# Board.net
KiCad netlist of a schematic drawn in EAGLE
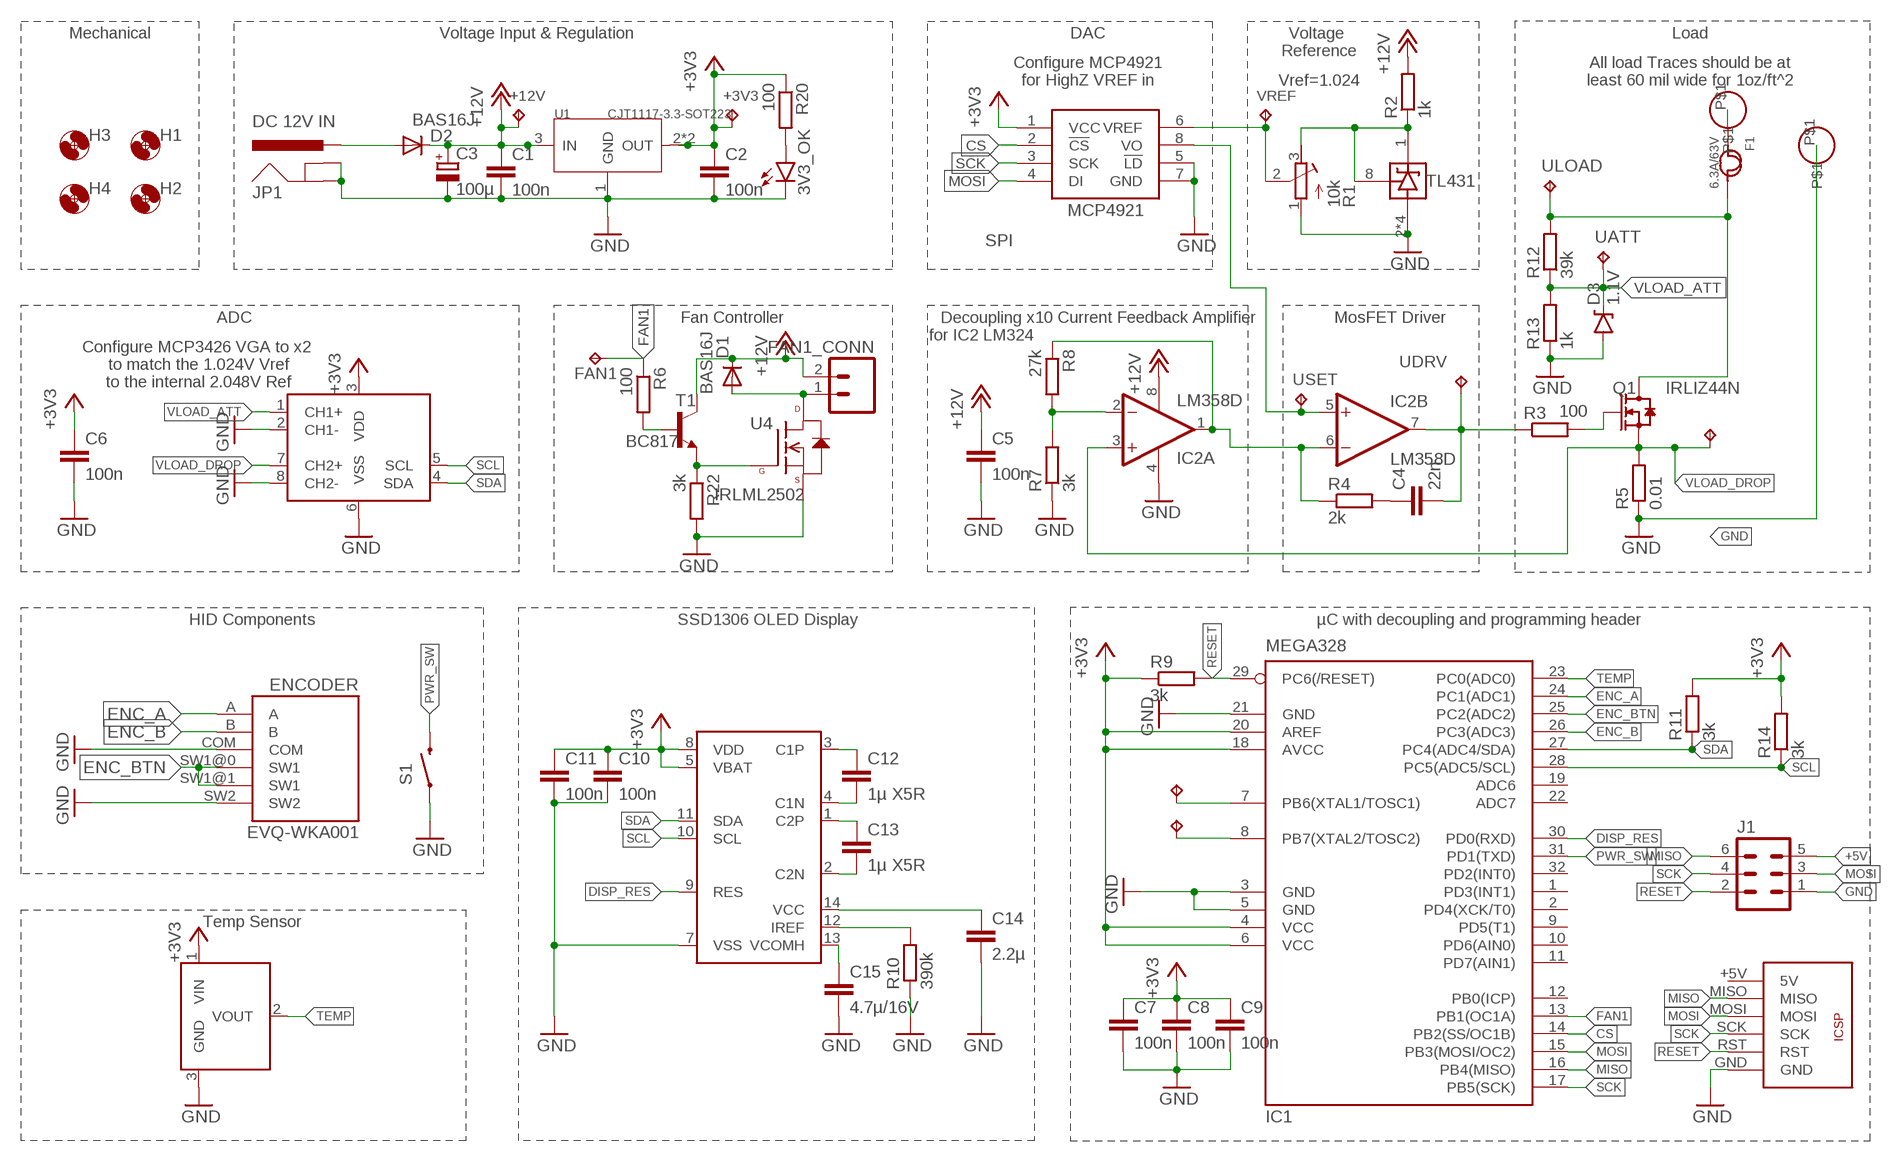
[diagram p0: schematic, sheet 1]

(export (version "E")
  (design (tool "Eeschema 10.0.6"))
  (components
    (comp (ref "+3V3")
      (value "TPB1,27")
      (footprint "eagle-import:B1,27")
      (libsource (lib "eagle-import") (part "TPB1,27"))
    )
    (comp (ref "+12V")
      (value "TPB1,27")
      (footprint "eagle-import:B1,27")
      (libsource (lib "eagle-import") (part "TPB1,27"))
    )
    (comp (ref "3V3_OK")
      (value "LED0603")
      (footprint "eagle-import:LED-0603")
      (libsource (lib "eagle-import") (part "LED0603"))
    )
    (comp (ref "C1")
      (value "100n")
      (footprint "eagle-import:C0603")
      (libsource (lib "eagle-import") (part "C-EUC0603"))
    )
    (comp (ref "C2")
      (value "100n")
      (footprint "eagle-import:C0603")
      (libsource (lib "eagle-import") (part "C-EUC0603"))
    )
    (comp (ref "C3")
      (value "100µ")
      (footprint "eagle-import:153CLV-0405")
      (libsource (lib "eagle-import") (part "CPOL-EU153CLV-0405"))
    )
    (comp (ref "C4")
      (value "22n")
      (footprint "eagle-import:C0603")
      (libsource (lib "eagle-import") (part "C-EUC0603"))
    )
    (comp (ref "C5")
      (value "100n")
      (footprint "eagle-import:C0603")
      (libsource (lib "eagle-import") (part "C-EUC0603"))
    )
    (comp (ref "C6")
      (value "100n")
      (footprint "eagle-import:C0603")
      (libsource (lib "eagle-import") (part "rcl_334_C-EUC0603"))
    )
    (comp (ref "C7")
      (value "100n")
      (footprint "eagle-import:C0603")
      (libsource (lib "eagle-import") (part "C-EUC0603"))
    )
    (comp (ref "C8")
      (value "100n")
      (footprint "eagle-import:C0603")
      (libsource (lib "eagle-import") (part "C-EUC0603"))
    )
    (comp (ref "C9")
      (value "100n")
      (footprint "eagle-import:C0603")
      (libsource (lib "eagle-import") (part "C-EUC0603"))
    )
    (comp (ref "C10")
      (value "100n")
      (footprint "eagle-import:C0603")
      (libsource (lib "eagle-import") (part "C-EUC0603"))
    )
    (comp (ref "C11")
      (value "100n")
      (footprint "eagle-import:C0603")
      (libsource (lib "eagle-import") (part "C-EUC0603"))
    )
    (comp (ref "C12")
      (value "1µ X5R")
      (footprint "eagle-import:C0603")
      (libsource (lib "eagle-import") (part "C-EUC0603"))
    )
    (comp (ref "C13")
      (value "1µ X5R")
      (footprint "eagle-import:C0603")
      (libsource (lib "eagle-import") (part "C-EUC0603"))
    )
    (comp (ref "C14")
      (value "2.2µ")
      (footprint "eagle-import:C0603")
      (libsource (lib "eagle-import") (part "C-EUC0603"))
    )
    (comp (ref "C15")
      (value "4.7µ/16V")
      (footprint "eagle-import:C0603")
      (libsource (lib "eagle-import") (part "C-EUC0603"))
    )
    (comp (ref "D1")
      (value "BAS16J")
      (footprint "eagle-import:SOD323-W")
      (libsource (lib "eagle-import") (part "DIODE-SOD323-W"))
    )
    (comp (ref "D2")
      (value "BAS16J")
      (footprint "eagle-import:SOD323-W")
      (libsource (lib "eagle-import") (part "DIODE-SOD323-W"))
    )
    (comp (ref "D3")
      (value "1.1V")
      (footprint "eagle-import:SOD-323")
      (libsource (lib "eagle-import") (part "DIODE-ZENER5.6V"))
    )
    (comp (ref "ENCODER")
      (value "EVQ-WKA001")
      (footprint "eagle-import:EVQ-WKA001")
      (libsource (lib "eagle-import") (part "EVQ-WKA001"))
    )
    (comp (ref "F1")
      (value "6.3A/63V")
      (footprint "eagle-import:F1206")
      (libsource (lib "eagle-import") (part "FUSE'1206'"))
    )
    (comp (ref "FAN1")
      (value "TPB1,27")
      (footprint "eagle-import:B1,27")
      (libsource (lib "eagle-import") (part "TPB1,27"))
    )
    (comp (ref "FAN1_CONN")
      (value "M02POLAR")
      (footprint "eagle-import:MOLEX-1X2")
      (libsource (lib "eagle-import") (part "M02POLAR"))
    )
    (comp (ref "H1")
      (value "MOUNT-HOLE3.0")
      (footprint "eagle-import:3,0")
      (libsource (lib "eagle-import") (part "MOUNT-HOLE3.0"))
    )
    (comp (ref "H2")
      (value "MOUNT-HOLE3.0")
      (footprint "eagle-import:3,0")
      (libsource (lib "eagle-import") (part "MOUNT-HOLE3.0"))
    )
    (comp (ref "H3")
      (value "MOUNT-HOLE3.0")
      (footprint "eagle-import:3,0")
      (libsource (lib "eagle-import") (part "MOUNT-HOLE3.0"))
    )
    (comp (ref "H4")
      (value "MOUNT-HOLE3.0")
      (footprint "eagle-import:3,0")
      (libsource (lib "eagle-import") (part "MOUNT-HOLE3.0"))
    )
    (comp (ref "IC1")
      (value "MEGA328")
      (footprint "eagle-import:TQFP32-08")
      (fields (field (name "MPN") "ATMEGA8-16AU"))
      (libsource (lib "eagle-import") (part "MEGA8-AI"))
    )
    (comp (ref "IC2")
      (value "LM358D")
      (footprint "eagle-import:SO08")
      (libsource (lib "eagle-import") (part "LM358D"))
    )
    (comp (ref "IC4")
      (value "MCP3426")
      (footprint "eagle-import:SO08")
      (libsource (lib "eagle-import") (part "MCP3426"))
    )
    (comp (ref "IC6")
      (value "MCP4921")
      (footprint "eagle-import:SO-8")
      (libsource (lib "eagle-import") (part "MCP4921"))
    )
    (comp (ref "IC7")
      (value "TL431CD")
      (footprint "eagle-import:SO-8")
      (libsource (lib "eagle-import") (part "TL431CD"))
    )
    (comp (ref "IN+")
      (value "6MM-BANANA-MOUNTINGHOLE")
      (footprint "eagle-import:6MM-BANANA-MOUNT")
      (libsource (lib "eagle-import") (part "6MM-BANANA-MOUNTINGHOLE"))
    )
    (comp (ref "IN-")
      (value "6MM-BANANA-MOUNTINGHOLE")
      (footprint "eagle-import:6MM-BANANA-MOUNT")
      (libsource (lib "eagle-import") (part "6MM-BANANA-MOUNTINGHOLE"))
    )
    (comp (ref "J1")
      (value "MA03-2")
      (footprint "eagle-import:MA03-2")
      (libsource (lib "eagle-import") (part "MA03-2"))
    )
    (comp (ref "JP1")
      (value "DC 12V IN")
      (footprint "eagle-import:POWER_JACK_PTH")
      (libsource (lib "eagle-import") (part "POWER_JACKPTH"))
    )
    (comp (ref "Q1")
      (value "IRLIZ44N")
      (footprint "eagle-import:TO-220H")
      (libsource (lib "eagle-import") (part "IRF3710"))
    )
    (comp (ref "R1")
      (value "10k")
      (footprint "eagle-import:RTRIM3296W")
      (libsource (lib "eagle-import") (part "R-TRIMM3296W"))
    )
    (comp (ref "R2")
      (value "1k")
      (footprint "eagle-import:R0603")
      (libsource (lib "eagle-import") (part "R-EU_R0603"))
    )
    (comp (ref "R3")
      (value "100")
      (footprint "eagle-import:R0603")
      (libsource (lib "eagle-import") (part "R-EU_R0603"))
    )
    (comp (ref "R4")
      (value "2k")
      (footprint "eagle-import:R0603")
      (libsource (lib "eagle-import") (part "R-EU_R0603"))
    )
    (comp (ref "R5")
      (value "0.01")
      (footprint "eagle-import:R2512")
      (libsource (lib "eagle-import") (part "R-EU_R2512"))
    )
    (comp (ref "R6")
      (value "100")
      (footprint "eagle-import:R0603")
      (libsource (lib "eagle-import") (part "rcl_334_R-EU_R0603"))
    )
    (comp (ref "R7")
      (value "3k")
      (footprint "eagle-import:R0603")
      (libsource (lib "eagle-import") (part "R-EU_R0603"))
    )
    (comp (ref "R8")
      (value "27k")
      (footprint "eagle-import:R0603")
      (libsource (lib "eagle-import") (part "R-EU_R0603"))
    )
    (comp (ref "R9")
      (value "3k")
      (footprint "eagle-import:R0603")
      (libsource (lib "eagle-import") (part "rcl_334_R-EU_R0603"))
    )
    (comp (ref "R10")
      (value "390k")
      (footprint "eagle-import:R0603")
      (libsource (lib "eagle-import") (part "R-EU_R0603"))
    )
    (comp (ref "R11")
      (value "3k")
      (footprint "eagle-import:R0603")
      (libsource (lib "eagle-import") (part "rcl_334_R-EU_R0603"))
    )
    (comp (ref "R12")
      (value "39k")
      (footprint "eagle-import:R0603")
      (libsource (lib "eagle-import") (part "R-EU_R0603"))
    )
    (comp (ref "R13")
      (value "1k")
      (footprint "eagle-import:R0603")
      (libsource (lib "eagle-import") (part "R-EU_R0603"))
    )
    (comp (ref "R14")
      (value "3k")
      (footprint "eagle-import:R0603")
      (libsource (lib "eagle-import") (part "rcl_334_R-EU_R0603"))
    )
    (comp (ref "R20")
      (value "100")
      (footprint "eagle-import:R0603")
      (libsource (lib "eagle-import") (part "R-EU_R0603"))
    )
    (comp (ref "R22")
      (value "3k")
      (footprint "eagle-import:R0603")
      (libsource (lib "eagle-import") (part "R-EU_R0603"))
    )
    (comp (ref "S1")
      (value "SWITCH-MOMENTARY-2SMD-1101NE")
      (footprint "eagle-import:TACTILE-SWITCH-1101NE")
      (libsource (lib "eagle-import") (part "SWITCH-MOMENTARY-2SMD-1101NE"))
    )
    (comp (ref "T1")
      (value "BC817")
      (footprint "eagle-import:SOT23-BEC")
      (libsource (lib "eagle-import") (part "-NPN-SOT23-BECBC817"))
    )
    (comp (ref "U$2")
      (value "0.86\"-OLEDBENT")
      (footprint "eagle-import:0.86_-OLED-BENT")
      (libsource (lib "eagle-import") (part "0.86{dblquote}-OLEDBENT"))
    )
    (comp (ref "U$4")
      (value "ICSP")
      (footprint "eagle-import:ICSP-SMD-NOSILK")
      (libsource (lib "eagle-import") (part "ICSP"))
    )
    (comp (ref "U1")
      (value "CJT1117-3.3-SOT223")
      (footprint "eagle-import:SOT-223")
      (fields (field (name "MPN") "CJT1117-3.3"))
      (libsource (lib "eagle-import") (part "PMIC-CJT1117-3.3(SOT223)"))
    )
    (comp (ref "U3")
      (value "MCP9701AT-E/TT")
      (footprint "eagle-import:SOT32-3")
      (libsource (lib "eagle-import") (part "MCP9701AT-E/TT"))
    )
    (comp (ref "U4")
      (value "IRLML2502")
      (footprint "eagle-import:SOT23-3")
      (libsource (lib "eagle-import") (part "N-CHANNEL-MOSFET-BSS138"))
    )
    (comp (ref "UATT")
      (value "TPB1,27")
      (footprint "eagle-import:B1,27")
      (libsource (lib "eagle-import") (part "TPB1,27"))
    )
    (comp (ref "UDROP")
      (value "TPB1,27")
      (footprint "eagle-import:B1,27")
      (libsource (lib "eagle-import") (part "TPB1,27"))
    )
    (comp (ref "UDRV")
      (value "TPB1,27")
      (footprint "eagle-import:B1,27")
      (libsource (lib "eagle-import") (part "TPB1,27"))
    )
    (comp (ref "ULOAD")
      (value "TPB1,27")
      (footprint "eagle-import:B1,27")
      (libsource (lib "eagle-import") (part "TPB1,27"))
    )
    (comp (ref "USET")
      (value "TPB1,27")
      (footprint "eagle-import:B1,27")
      (libsource (lib "eagle-import") (part "TPB1,27"))
    )
    (comp (ref "VREF")
      (value "TPB1,27")
      (footprint "eagle-import:B1,27")
      (libsource (lib "eagle-import") (part "TPB1,27"))
    )
    (comp (ref "XTAL1")
      (value "TPB1,27")
      (footprint "eagle-import:B1,27")
      (libsource (lib "eagle-import") (part "TPB1,27"))
    )
    (comp (ref "XTAL2")
      (value "TPB1,27")
      (footprint "eagle-import:B1,27")
      (libsource (lib "eagle-import") (part "TPB1,27"))
    )
  )
  (nets
    (net (code "1") (name "+3V3") (class "Default")
      (node (ref "+3V3") (pin "TP") (pinfunction "TP_TP") (pintype "input"))
      (node (ref "C10") (pin "1") (pinfunction "1_1") (pintype "passive"))
      (node (ref "C11") (pin "1") (pinfunction "1_1") (pintype "passive"))
      (node (ref "C2") (pin "1") (pinfunction "1_1") (pintype "passive"))
      (node (ref "C6") (pin "1") (pinfunction "1_1") (pintype "passive"))
      (node (ref "C7") (pin "1") (pinfunction "1_1") (pintype "passive"))
      (node (ref "C8") (pin "1") (pinfunction "1_1") (pintype "passive"))
      (node (ref "C9") (pin "1") (pinfunction "1_1") (pintype "passive"))
      (node (ref "IC1") (pin "18") (pinfunction "AVCC_18") (pintype "power_in"))
      (node (ref "IC1") (pin "20") (pinfunction "AREF_20") (pintype "passive"))
      (node (ref "IC1") (pin "4") (pinfunction "VCC_4") (pintype "power_in"))
      (node (ref "IC1") (pin "6") (pinfunction "VCC_6") (pintype "power_in"))
      (node (ref "IC4") (pin "3") (pinfunction "VDD_3") (pintype "bidirectional"))
      (node (ref "IC6") (pin "1") (pinfunction "VCC_1") (pintype "power_in"))
      (node (ref "R11") (pin "2") (pinfunction "2_2") (pintype "passive"))
      (node (ref "R14") (pin "2") (pinfunction "2_2") (pintype "passive"))
      (node (ref "R20") (pin "1") (pinfunction "1_1") (pintype "passive"))
      (node (ref "R9") (pin "1") (pinfunction "1_1") (pintype "passive"))
      (node (ref "U$2") (pin "5") (pinfunction "VBAT_5") (pintype "bidirectional"))
      (node (ref "U$2") (pin "8") (pinfunction "VDD_8") (pintype "bidirectional"))
      (node (ref "U1") (pin "2") (pinfunction "OUT_2") (pintype "bidirectional"))
      (node (ref "U1") (pin "TER") (pinfunction "OUT_TER") (pintype "bidirectional"))
      (node (ref "U3") (pin "1") (pinfunction "VIN_1") (pintype "bidirectional"))
    )
    (net (code "2") (name "+5V") (class "Default")
      (node (ref "J1") (pin "5") (pinfunction "5_5") (pintype "passive"))
    )
    (net (code "3") (name "+12V") (class "Default")
      (node (ref "+12V") (pin "TP") (pinfunction "TP_TP") (pintype "input"))
      (node (ref "C1") (pin "1") (pinfunction "1_1") (pintype "passive"))
      (node (ref "C3") (pin "+") (pinfunction "+_+") (pintype "passive"))
      (node (ref "C5") (pin "1") (pinfunction "1_1") (pintype "passive"))
      (node (ref "D1") (pin "C") (pinfunction "C_C") (pintype "passive"))
      (node (ref "D2") (pin "C") (pinfunction "C_C") (pintype "passive"))
      (node (ref "FAN1_CONN") (pin "2") (pinfunction "2_2") (pintype "passive"))
      (node (ref "IC2") (pin "8") (pinfunction "V+_8") (pintype "power_in"))
      (node (ref "R2") (pin "2") (pinfunction "2_2") (pintype "passive"))
      (node (ref "T1") (pin "C") (pinfunction "C_C") (pintype "passive"))
      (node (ref "U1") (pin "3") (pinfunction "IN_3") (pintype "bidirectional"))
    )
    (net (code "4") (name "CS") (class "Default")
      (node (ref "IC1") (pin "14") (pinfunction "PB2(SS/OC1B)_14") (pintype "bidirectional"))
      (node (ref "IC6") (pin "2") (pinfunction "~{CS}_2") (pintype "bidirectional"))
    )
    (net (code "5") (name "DISP_RES") (class "Default")
      (node (ref "IC1") (pin "30") (pinfunction "PD0(RXD)_30") (pintype "bidirectional"))
      (node (ref "U$2") (pin "9") (pinfunction "RES_9") (pintype "bidirectional"))
    )
    (net (code "6") (name "ENC_A") (class "Default")
      (node (ref "ENCODER") (pin "A") (pinfunction "A_A") (pintype "bidirectional"))
      (node (ref "IC1") (pin "24") (pinfunction "PC1(ADC1)_24") (pintype "bidirectional"))
    )
    (net (code "7") (name "ENC_B") (class "Default")
      (node (ref "ENCODER") (pin "B") (pinfunction "B_B") (pintype "bidirectional"))
      (node (ref "IC1") (pin "26") (pinfunction "PC3(ADC3)_26") (pintype "bidirectional"))
    )
    (net (code "8") (name "ENC_BTN") (class "Default")
      (node (ref "ENCODER") (pin "SW1@0") (pinfunction "SW1_SW1@0") (pintype "bidirectional"))
      (node (ref "ENCODER") (pin "SW1@1") (pinfunction "SW1_SW1@1") (pintype "bidirectional"))
      (node (ref "IC1") (pin "25") (pinfunction "PC2(ADC2)_25") (pintype "bidirectional"))
    )
    (net (code "9") (name "FAN1") (class "Default")
      (node (ref "FAN1") (pin "TP") (pinfunction "TP_TP") (pintype "input"))
      (node (ref "IC1") (pin "13") (pinfunction "PB1(OC1A)_13") (pintype "bidirectional"))
      (node (ref "R6") (pin "1") (pinfunction "1_1") (pintype "passive"))
    )
    (net (code "10") (name "GND") (class "Default")
      (node (ref "3V3_OK") (pin "C") (pinfunction "C_C") (pintype "passive"))
      (node (ref "C1") (pin "2") (pinfunction "2_2") (pintype "passive"))
      (node (ref "C10") (pin "2") (pinfunction "2_2") (pintype "passive"))
      (node (ref "C11") (pin "2") (pinfunction "2_2") (pintype "passive"))
      (node (ref "C14") (pin "2") (pinfunction "2_2") (pintype "passive"))
      (node (ref "C15") (pin "2") (pinfunction "2_2") (pintype "passive"))
      (node (ref "C2") (pin "2") (pinfunction "2_2") (pintype "passive"))
      (node (ref "C3") (pin "-") (pinfunction "-_-") (pintype "passive"))
      (node (ref "C5") (pin "2") (pinfunction "2_2") (pintype "passive"))
      (node (ref "C6") (pin "2") (pinfunction "2_2") (pintype "passive"))
      (node (ref "C7") (pin "2") (pinfunction "2_2") (pintype "passive"))
      (node (ref "C8") (pin "2") (pinfunction "2_2") (pintype "passive"))
      (node (ref "C9") (pin "2") (pinfunction "2_2") (pintype "passive"))
      (node (ref "D3") (pin "A") (pinfunction "A_A") (pintype "passive"))
      (node (ref "ENCODER") (pin "COM") (pinfunction "COM_COM") (pintype "bidirectional"))
      (node (ref "ENCODER") (pin "SW2") (pinfunction "SW2_SW2") (pintype "bidirectional"))
      (node (ref "IC1") (pin "21") (pinfunction "GND_21") (pintype "power_in"))
      (node (ref "IC1") (pin "3") (pinfunction "GND_3") (pintype "power_in"))
      (node (ref "IC1") (pin "5") (pinfunction "GND_5") (pintype "power_in"))
      (node (ref "IC2") (pin "4") (pinfunction "V-_4") (pintype "power_in"))
      (node (ref "IC4") (pin "2") (pinfunction "CH1-_2") (pintype "bidirectional"))
      (node (ref "IC4") (pin "6") (pinfunction "VSS_6") (pintype "bidirectional"))
      (node (ref "IC4") (pin "8") (pinfunction "CH2-_8") (pintype "bidirectional"))
      (node (ref "IC6") (pin "5") (pinfunction "~{LD}_5") (pintype "input"))
      (node (ref "IC6") (pin "7") (pinfunction "GND_7") (pintype "power_in"))
      (node (ref "IC7") (pin "2") (pinfunction "ANODE_2") (pintype "passive"))
      (node (ref "IC7") (pin "3") (pinfunction "ANODE_3") (pintype "passive"))
      (node (ref "IC7") (pin "6") (pinfunction "ANODE_6") (pintype "passive"))
      (node (ref "IC7") (pin "7") (pinfunction "ANODE_7") (pintype "passive"))
      (node (ref "IN-") (pin "P$1") (pinfunction "P$1_P$1") (pintype "bidirectional"))
      (node (ref "J1") (pin "1") (pinfunction "1_1") (pintype "passive"))
      (node (ref "JP1") (pin "GND") (pinfunction "GND_GND") (pintype "bidirectional"))
      (node (ref "JP1") (pin "GNDBREAK") (pinfunction "GNDBREAK_GNDBREAK") (pintype "bidirectional"))
      (node (ref "R1") (pin "1") (pinfunction "A_1") (pintype "passive"))
      (node (ref "R10") (pin "1") (pinfunction "1_1") (pintype "passive"))
      (node (ref "R13") (pin "1") (pinfunction "1_1") (pintype "passive"))
      (node (ref "R22") (pin "2") (pinfunction "2_2") (pintype "passive"))
      (node (ref "R5") (pin "1") (pinfunction "1_1") (pintype "passive"))
      (node (ref "R7") (pin "1") (pinfunction "1_1") (pintype "passive"))
      (node (ref "S1") (pin "1") (pinfunction "1_1") (pintype "passive"))
      (node (ref "U$2") (pin "7") (pinfunction "VSS_7") (pintype "bidirectional"))
      (node (ref "U$4") (pin "GND") (pinfunction "GND_GND") (pintype "bidirectional"))
      (node (ref "U1") (pin "1") (pinfunction "GND_1") (pintype "bidirectional"))
      (node (ref "U3") (pin "3") (pinfunction "GND_3") (pintype "bidirectional"))
      (node (ref "U4") (pin "2") (pinfunction "S_2") (pintype "passive"))
    )
    (net (code "11") (name "MISO") (class "Default")
      (node (ref "IC1") (pin "16") (pinfunction "PB4(MISO)_16") (pintype "bidirectional"))
      (node (ref "J1") (pin "6") (pinfunction "6_6") (pintype "passive"))
      (node (ref "U$4") (pin "MISO") (pinfunction "MISO_MISO") (pintype "bidirectional"))
    )
    (net (code "12") (name "MOSI") (class "Default")
      (node (ref "IC1") (pin "15") (pinfunction "PB3(MOSI/OC2)_15") (pintype "bidirectional"))
      (node (ref "IC6") (pin "4") (pinfunction "DI_4") (pintype "bidirectional"))
      (node (ref "J1") (pin "3") (pinfunction "3_3") (pintype "passive"))
      (node (ref "U$4") (pin "MOSI") (pinfunction "MOSI_MOSI") (pintype "bidirectional"))
    )
    (net (code "13") (name "Net-(3V3_OK-PadA)") (class "Default")
      (node (ref "3V3_OK") (pin "A") (pinfunction "A_A") (pintype "passive"))
      (node (ref "R20") (pin "2") (pinfunction "2_2") (pintype "passive"))
    )
    (net (code "14") (name "Net-(C4-Pad1)") (class "Default")
      (node (ref "C4") (pin "1") (pinfunction "1_1") (pintype "passive"))
      (node (ref "R4") (pin "2") (pinfunction "2_2") (pintype "passive"))
    )
    (net (code "15") (name "Net-(D2-PadA)") (class "Default")
      (node (ref "D2") (pin "A") (pinfunction "A_A") (pintype "passive"))
      (node (ref "JP1") (pin "PWR") (pinfunction "PWR_PWR") (pintype "bidirectional"))
    )
    (net (code "16") (name "Net-(F1-Pad1)") (class "Default")
      (node (ref "F1") (pin "1") (pinfunction "1_1") (pintype "bidirectional"))
      (node (ref "IN+") (pin "P$1") (pinfunction "P$1_P$1") (pintype "bidirectional"))
    )
    (net (code "17") (name "Net-(IC1-PB6(XTAL1{slash}TOSC1))") (class "Default")
      (node (ref "IC1") (pin "7") (pinfunction "PB6(XTAL1/TOSC1)_7") (pintype "bidirectional"))
      (node (ref "XTAL1") (pin "TP") (pinfunction "TP_TP") (pintype "input"))
    )
    (net (code "18") (name "Net-(IC1-PB7(XTAL2{slash}TOSC2))") (class "Default")
      (node (ref "IC1") (pin "8") (pinfunction "PB7(XTAL2/TOSC2)_8") (pintype "bidirectional"))
      (node (ref "XTAL2") (pin "TP") (pinfunction "TP_TP") (pintype "input"))
    )
    (net (code "19") (name "Net-(IC2A--IN)") (class "Default")
      (node (ref "IC2") (pin "2") (pinfunction "-IN_2") (pintype "input"))
      (node (ref "R7") (pin "2") (pinfunction "2_2") (pintype "passive"))
      (node (ref "R8") (pin "2") (pinfunction "2_2") (pintype "passive"))
    )
    (net (code "20") (name "Net-(IC2A-OUT)") (class "Default")
      (node (ref "IC2") (pin "1") (pinfunction "OUT_1") (pintype "output"))
      (node (ref "IC2") (pin "6") (pinfunction "-IN_6") (pintype "input"))
      (node (ref "R4") (pin "1") (pinfunction "1_1") (pintype "passive"))
      (node (ref "R8") (pin "1") (pinfunction "1_1") (pintype "passive"))
    )
    (net (code "21") (name "Net-(IC2B-+IN)") (class "Default")
      (node (ref "IC2") (pin "5") (pinfunction "+IN_5") (pintype "input"))
      (node (ref "IC6") (pin "8") (pinfunction "VO_8") (pintype "output"))
      (node (ref "USET") (pin "TP") (pinfunction "TP_TP") (pintype "input"))
    )
    (net (code "22") (name "Net-(IC2B-OUT)") (class "Default")
      (node (ref "C4") (pin "2") (pinfunction "2_2") (pintype "passive"))
      (node (ref "IC2") (pin "7") (pinfunction "OUT_7") (pintype "output"))
      (node (ref "R3") (pin "1") (pinfunction "1_1") (pintype "passive"))
      (node (ref "UDRV") (pin "TP") (pinfunction "TP_TP") (pintype "input"))
    )
    (net (code "23") (name "Net-(IC6-VREF)") (class "Default")
      (node (ref "IC6") (pin "6") (pinfunction "VREF_6") (pintype "input"))
      (node (ref "R1") (pin "2") (pinfunction "S_2") (pintype "passive"))
      (node (ref "VREF") (pin "TP") (pinfunction "TP_TP") (pintype "input"))
    )
    (net (code "24") (name "Net-(IC7-CATHODE)") (class "Default")
      (node (ref "IC7") (pin "1") (pinfunction "CATHODE_1") (pintype "passive"))
      (node (ref "IC7") (pin "8") (pinfunction "REF_8") (pintype "passive"))
      (node (ref "R1") (pin "3") (pinfunction "E_3") (pintype "passive"))
      (node (ref "R2") (pin "1") (pinfunction "1_1") (pintype "passive"))
    )
    (net (code "25") (name "Net-(Q1-D)") (class "Default")
      (node (ref "F1") (pin "2") (pinfunction "2_2") (pintype "bidirectional"))
      (node (ref "Q1") (pin "P$2") (pinfunction "D_P$2") (pintype "passive"))
      (node (ref "R12") (pin "2") (pinfunction "2_2") (pintype "passive"))
      (node (ref "ULOAD") (pin "TP") (pinfunction "TP_TP") (pintype "input"))
    )
    (net (code "26") (name "Net-(Q1-G)") (class "Default")
      (node (ref "Q1") (pin "P$1") (pinfunction "G_P$1") (pintype "passive"))
      (node (ref "R3") (pin "2") (pinfunction "2_2") (pintype "passive"))
    )
    (net (code "27") (name "Net-(R6-Pad2)") (class "Default")
      (node (ref "R6") (pin "2") (pinfunction "2_2") (pintype "passive"))
      (node (ref "T1") (pin "B") (pinfunction "B_B") (pintype "passive"))
    )
    (net (code "28") (name "Net-(U$2-C1N)") (class "Default")
      (node (ref "C12") (pin "2") (pinfunction "2_2") (pintype "passive"))
      (node (ref "U$2") (pin "4") (pinfunction "C1N_4") (pintype "bidirectional"))
    )
    (net (code "29") (name "Net-(U$2-C1P)") (class "Default")
      (node (ref "C12") (pin "1") (pinfunction "1_1") (pintype "passive"))
      (node (ref "U$2") (pin "3") (pinfunction "C1P_3") (pintype "bidirectional"))
    )
    (net (code "30") (name "Net-(U$2-C2N)") (class "Default")
      (node (ref "C13") (pin "2") (pinfunction "2_2") (pintype "passive"))
      (node (ref "U$2") (pin "2") (pinfunction "C2N_2") (pintype "bidirectional"))
    )
    (net (code "31") (name "Net-(U$2-C2P)") (class "Default")
      (node (ref "C13") (pin "1") (pinfunction "1_1") (pintype "passive"))
      (node (ref "U$2") (pin "1") (pinfunction "C2P_1") (pintype "bidirectional"))
    )
    (net (code "32") (name "Net-(U$2-IREF)") (class "Default")
      (node (ref "R10") (pin "2") (pinfunction "2_2") (pintype "passive"))
      (node (ref "U$2") (pin "12") (pinfunction "IREF_12") (pintype "bidirectional"))
    )
    (net (code "33") (name "Net-(U$2-VCC)") (class "Default")
      (node (ref "C14") (pin "1") (pinfunction "1_1") (pintype "passive"))
      (node (ref "U$2") (pin "14") (pinfunction "VCC_14") (pintype "bidirectional"))
    )
    (net (code "34") (name "Net-(U$2-VCOMH)") (class "Default")
      (node (ref "C15") (pin "1") (pinfunction "1_1") (pintype "passive"))
      (node (ref "U$2") (pin "13") (pinfunction "VCOMH_13") (pintype "bidirectional"))
    )
    (net (code "35") (name "Net-(U4-D)") (class "Default")
      (node (ref "D1") (pin "A") (pinfunction "A_A") (pintype "passive"))
      (node (ref "FAN1_CONN") (pin "1") (pinfunction "1_1") (pintype "passive"))
      (node (ref "U4") (pin "3") (pinfunction "D_3") (pintype "passive"))
    )
    (net (code "36") (name "Net-(U4-G)") (class "Default")
      (node (ref "R22") (pin "1") (pinfunction "1_1") (pintype "passive"))
      (node (ref "T1") (pin "E") (pinfunction "E_E") (pintype "passive"))
      (node (ref "U4") (pin "1") (pinfunction "G_1") (pintype "passive"))
    )
    (net (code "37") (name "PWR_SW") (class "Default")
      (node (ref "IC1") (pin "31") (pinfunction "PD1(TXD)_31") (pintype "bidirectional"))
      (node (ref "S1") (pin "2") (pinfunction "2_2") (pintype "passive"))
    )
    (net (code "38") (name "RESET") (class "Default")
      (node (ref "IC1") (pin "29") (pinfunction "PC6(/RESET)_29") (pintype "bidirectional"))
      (node (ref "J1") (pin "2") (pinfunction "2_2") (pintype "passive"))
      (node (ref "R9") (pin "2") (pinfunction "2_2") (pintype "passive"))
      (node (ref "U$4") (pin "RST") (pinfunction "RST_RST") (pintype "bidirectional"))
    )
    (net (code "39") (name "SCK") (class "Default")
      (node (ref "IC1") (pin "17") (pinfunction "PB5(SCK)_17") (pintype "bidirectional"))
      (node (ref "IC6") (pin "3") (pinfunction "SCK_3") (pintype "bidirectional"))
      (node (ref "J1") (pin "4") (pinfunction "4_4") (pintype "passive"))
      (node (ref "U$4") (pin "SCK") (pinfunction "SCK_SCK") (pintype "bidirectional"))
    )
    (net (code "40") (name "SCL") (class "Default")
      (node (ref "IC1") (pin "28") (pinfunction "PC5(ADC5/SCL)_28") (pintype "bidirectional"))
      (node (ref "IC4") (pin "5") (pinfunction "SCL_5") (pintype "bidirectional"))
      (node (ref "R14") (pin "1") (pinfunction "1_1") (pintype "passive"))
      (node (ref "U$2") (pin "10") (pinfunction "SCL_10") (pintype "bidirectional"))
    )
    (net (code "41") (name "SDA") (class "Default")
      (node (ref "IC1") (pin "27") (pinfunction "PC4(ADC4/SDA)_27") (pintype "bidirectional"))
      (node (ref "IC4") (pin "4") (pinfunction "SDA_4") (pintype "bidirectional"))
      (node (ref "R11") (pin "1") (pinfunction "1_1") (pintype "passive"))
      (node (ref "U$2") (pin "11") (pinfunction "SDA_11") (pintype "bidirectional"))
    )
    (net (code "42") (name "TEMP") (class "Default")
      (node (ref "IC1") (pin "23") (pinfunction "PC0(ADC0)_23") (pintype "bidirectional"))
      (node (ref "U3") (pin "2") (pinfunction "VOUT_2") (pintype "bidirectional"))
    )
    (net (code "43") (name "VLOAD_ATT") (class "Default")
      (node (ref "D3") (pin "C") (pinfunction "C_C") (pintype "passive"))
      (node (ref "IC4") (pin "1") (pinfunction "CH1+_1") (pintype "bidirectional"))
      (node (ref "R12") (pin "1") (pinfunction "1_1") (pintype "passive"))
      (node (ref "R13") (pin "2") (pinfunction "2_2") (pintype "passive"))
      (node (ref "UATT") (pin "TP") (pinfunction "TP_TP") (pintype "input"))
    )
    (net (code "44") (name "VLOAD_DROP") (class "Default")
      (node (ref "IC2") (pin "3") (pinfunction "+IN_3") (pintype "input"))
      (node (ref "IC4") (pin "7") (pinfunction "CH2+_7") (pintype "bidirectional"))
      (node (ref "Q1") (pin "P$3") (pinfunction "S_P$3") (pintype "passive"))
      (node (ref "R5") (pin "2") (pinfunction "2_2") (pintype "passive"))
      (node (ref "UDROP") (pin "TP") (pinfunction "TP_TP") (pintype "input"))
    )
    (net (code "45") (name "unconnected-(IC1-ADC6-Pad19)") (class "Default")
      (node (ref "IC1") (pin "19") (pinfunction "ADC6_19") (pintype "bidirectional"))
    )
    (net (code "46") (name "unconnected-(IC1-ADC7-Pad22)") (class "Default")
      (node (ref "IC1") (pin "22") (pinfunction "ADC7_22") (pintype "bidirectional"))
    )
    (net (code "47") (name "unconnected-(IC1-PB0(ICP)-Pad12)") (class "Default")
      (node (ref "IC1") (pin "12") (pinfunction "PB0(ICP)_12") (pintype "bidirectional"))
    )
    (net (code "48") (name "unconnected-(IC1-PD2(INT0)-Pad32)") (class "Default")
      (node (ref "IC1") (pin "32") (pinfunction "PD2(INT0)_32") (pintype "bidirectional"))
    )
    (net (code "49") (name "unconnected-(IC1-PD3(INT1)-Pad1)") (class "Default")
      (node (ref "IC1") (pin "1") (pinfunction "PD3(INT1)_1") (pintype "bidirectional"))
    )
    (net (code "50") (name "unconnected-(IC1-PD4(XCK{slash}T0)-Pad2)") (class "Default")
      (node (ref "IC1") (pin "2") (pinfunction "PD4(XCK/T0)_2") (pintype "bidirectional"))
    )
    (net (code "51") (name "unconnected-(IC1-PD5(T1)-Pad9)") (class "Default")
      (node (ref "IC1") (pin "9") (pinfunction "PD5(T1)_9") (pintype "bidirectional"))
    )
    (net (code "52") (name "unconnected-(IC1-PD6(AIN0)-Pad10)") (class "Default")
      (node (ref "IC1") (pin "10") (pinfunction "PD6(AIN0)_10") (pintype "bidirectional"))
    )
    (net (code "53") (name "unconnected-(IC1-PD7(AIN1)-Pad11)") (class "Default")
      (node (ref "IC1") (pin "11") (pinfunction "PD7(AIN1)_11") (pintype "bidirectional"))
    )
    (net (code "54") (name "unconnected-(U$4-5V-Pad+5V)") (class "Default")
      (node (ref "U$4") (pin "+5V") (pinfunction "5V_+5V") (pintype "bidirectional"))
    )
  )
)
